# PowerBoard-OLD.net
KiCad netlist of a schematic drawn in Altium Designer
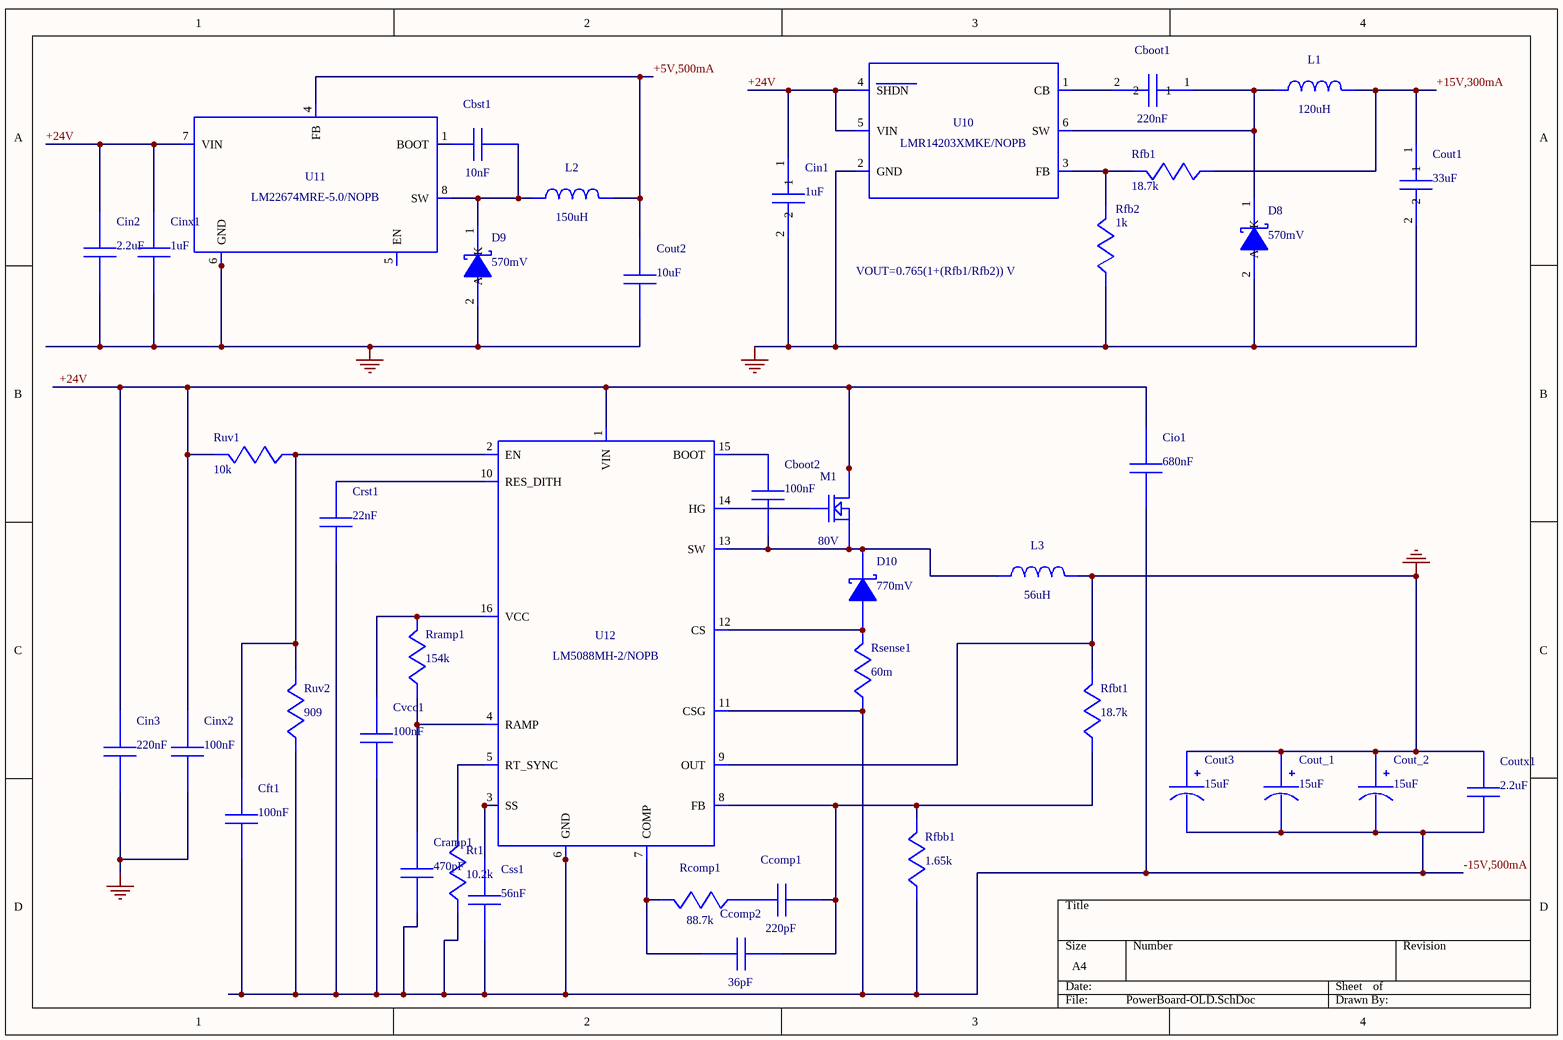
[diagram p0: PowerBoard-OLD.SchDoc]

(export (version "E")
  (design (tool "Eeschema 10.0.6"))
  (components
    (comp (ref "Cboot1")
      (value "220nF")
      (description "GRM155C80G224KE0")
      (fields (field (name "MANUFACTURER PART NUMBER") "GRM155C80G224KE01D"))
      (libsource (lib "TI WEBENCH") (part "Cboot"))
    )
    (comp (ref "Cboot2")
      (value "100nF")
      (description "C0603C104K5RACTU")
      (libsource (lib "") (part "Cboot_1"))
    )
    (comp (ref "Cbst1")
      (value "10nF")
      (description "C0805C103K5RACTU")
      (libsource (lib "TI WEBENCH") (part "Cbst"))
    )
    (comp (ref "Ccomp1")
      (value "220pF")
      (description "CC0805JRNPO9BN22")
      (fields (field (name "MANUFACTURER PART NUMBER") "CC0805JRNPO9BN221"))
      (libsource (lib "TI WEBENCH") (part "Ccomp"))
    )
    (comp (ref "Ccomp2")
      (value "36pF")
      (description "CL21C360JBANNNC")
      (libsource (lib "TI WEBENCH") (part "Ccomp2"))
    )
    (comp (ref "Cft1")
      (value "100nF")
      (description "GRM155R61A104KA0")
      (fields (field (name "MANUFACTURER PART NUMBER") "GRM155R61A104KA01D"))
      (libsource (lib "TI WEBENCH") (part "Cft"))
    )
    (comp (ref "Cin1")
      (value "1uF")
      (description "C1608X5R1H105K08")
      (fields (field (name "MANUFACTURER PART NUMBER") "C1608X5R1H105K080AB"))
      (libsource (lib "") (part "Cin_1"))
    )
    (comp (ref "Cin2")
      (value "2.2uF")
      (description "GRM31CR71H225KA8")
      (fields (field (name "MANUFACTURER PART NUMBER") "GRM31CR71H225KA88L"))
      (libsource (lib "TI WEBENCH") (part "Cin"))
    )
    (comp (ref "Cin3")
      (value "220nF")
      (description "C0805C224K5RACTU")
      (libsource (lib "TI WEBENCH") (part "Cin"))
    )
    (comp (ref "Cinx1")
      (value "1uF")
      (description "C1608X5R1H105K08")
      (fields (field (name "MANUFACTURER PART NUMBER") "C1608X5R1H105K080AB"))
      (libsource (lib "TI WEBENCH") (part "Cinx"))
    )
    (comp (ref "Cinx2")
      (value "100nF")
      (description "C0805C104K5RACTU")
      (libsource (lib "TI WEBENCH") (part "Cinx"))
    )
    (comp (ref "Cio1")
      (value "680nF")
      (description "C2012X7S2A684K12")
      (fields (field (name "MANUFACTURER PART NUMBER") "C2012X7S2A684K125AB"))
      (libsource (lib "TI WEBENCH") (part "Cio"))
    )
    (comp (ref "Cout1")
      (value "33uF")
      (description "C3216X5R1E336M16")
      (fields (field (name "MANUFACTURER PART NUMBER") "C3216X5R1E336M160AC"))
      (libsource (lib "TI WEBENCH") (part "Cout"))
    )
    (comp (ref "Cout2") (value "10uF") (description "C0805C106K8PACTU") (libsource (lib "") (part "Cout_2")))
    (comp (ref "Cout3")
      (value "15uF")
      (description "T495C156K020ATE3")
      (fields (field (name "MANUFACTURER PART NUMBER") "T495C156K020ATE375"))
      (libsource (lib "") (part "Cout_1"))
    )
    (comp (ref "Coutx1")
      (value "2.2uF")
      (description "GRM21BR61E225KA1")
      (fields (field (name "MANUFACTURER PART NUMBER") "GRM21BR61E225KA12L"))
      (libsource (lib "TI WEBENCH") (part "Coutx"))
    )
    (comp (ref "Cout_1")
      (value "15uF")
      (description "T495C156K020ATE3")
      (fields (field (name "MANUFACTURER PART NUMBER") "T495C156K020ATE375"))
      (libsource (lib "TI WEBENCH") (part "Cout_2"))
    )
    (comp (ref "Cout_2")
      (value "15uF")
      (description "T495C156K020ATE3")
      (fields (field (name "MANUFACTURER PART NUMBER") "T495C156K020ATE375"))
      (libsource (lib "TI WEBENCH") (part "Cout_3"))
    )
    (comp (ref "Cramp1")
      (value "470pF")
      (description "CC0805KRX7R9BB47")
      (fields (field (name "MANUFACTURER PART NUMBER") "CC0805KRX7R9BB471"))
      (libsource (lib "TI WEBENCH") (part "Cramp"))
    )
    (comp (ref "Crst1")
      (value "22nF")
      (description "GRM033C80J223KE0")
      (fields (field (name "MANUFACTURER PART NUMBER") "GRM033C80J223KE01D"))
      (libsource (lib "TI WEBENCH") (part "Crst"))
    )
    (comp (ref "Css1")
      (value "56nF")
      (description "GRM155R61A563KA0")
      (fields (field (name "MANUFACTURER PART NUMBER") "GRM155R61A563KA01D"))
      (libsource (lib "TI WEBENCH") (part "Css"))
    )
    (comp (ref "Cvcc1")
      (value "100nF")
      (description "GRM155R61A104KA0")
      (fields (field (name "MANUFACTURER PART NUMBER") "GRM155R61A104KA01D"))
      (libsource (lib "TI WEBENCH") (part "Cvcc"))
    )
    (comp (ref "D8")
      (value "570mV")
      (description "PMEG6010CEH,115")
      (libsource (lib "TI WEBENCH") (part "D1"))
    )
    (comp (ref "D9")
      (value "570mV")
      (description "PMEG6010CEH,115")
      (libsource (lib "TI WEBENCH") (part "D1"))
    )
    (comp (ref "D10") (value "770mV") (description "DFLS1100-7") (libsource (lib "") (part "D1_1")))
    (comp (ref "L1") (value "120uH") (description "NPI75C121KTRF") (libsource (lib "TI WEBENCH") (part "L1")))
    (comp (ref "L2")
      (value "150uH")
      (description "Unknown")
      (fields (field (name "MANUFACTURER PART NUMBER") "VLP8040T-151M"))
      (libsource (lib "TI WEBENCH") (part "L1"))
    )
    (comp (ref "L3") (value "56uH") (description "SDR1307-560KL") (libsource (lib "TI WEBENCH") (part "L1")))
    (comp (ref "M1") (value "80V") (description "BSC340N08NS3 G") (libsource (lib "TI WEBENCH") (part "M1")))
    (comp (ref "Rcomp1")
      (value "88.7k")
      (description "CRCW040288K7FKED")
      (libsource (lib "TI WEBENCH") (part "Rcomp"))
    )
    (comp (ref "Rfb1")
      (value "18.7k")
      (description "CRCW040218K7FKED")
      (libsource (lib "TI WEBENCH") (part "Rfb2"))
    )
    (comp (ref "Rfb2")
      (value "1k")
      (description "CRCW04021K00FKED")
      (libsource (lib "TI WEBENCH") (part "Rfb1"))
    )
    (comp (ref "Rfbb1")
      (value "1.65k")
      (description "CRCW04021K65FKED")
      (libsource (lib "TI WEBENCH") (part "Rfbb"))
    )
    (comp (ref "Rfbt1")
      (value "18.7k")
      (description "CRCW040218K7FKED")
      (libsource (lib "TI WEBENCH") (part "Rfbt"))
    )
    (comp (ref "Rramp1")
      (value "154k")
      (description "CRCW0402154KFKED")
      (libsource (lib "TI WEBENCH") (part "Rramp"))
    )
    (comp (ref "Rsense1")
      (value "60m")
      (description "CSRN2010FK60L0")
      (libsource (lib "TI WEBENCH") (part "Rsense"))
    )
    (comp (ref "Rt1")
      (value "10.2k")
      (description "CRCW040210K2FKED")
      (libsource (lib "TI WEBENCH") (part "Rt"))
    )
    (comp (ref "Ruv1")
      (value "10k")
      (description "CRCW040210K0FKED")
      (libsource (lib "TI WEBENCH") (part "Ruv2"))
    )
    (comp (ref "Ruv2")
      (value "909")
      (description "CRCW0402909RFKED")
      (libsource (lib "TI WEBENCH") (part "Ruv1"))
    )
    (comp (ref "U10")
      (value "LMR14203XMK/NOPB")
      (description "LMR14203XMKE/NOP")
      (fields (field (name "PACKAGEREFERENCE") "LMR14203XMKE/NOPB"))
      (libsource (lib "") (part "U1_1"))
    )
    (comp (ref "U11")
      (value "LM22674MRE-5.0/NOPB")
      (description "LM22674MRE-5.0/N")
      (fields (field (name "PACKAGEREFERENCE") "LM22674MRE-5.0/NOPB"))
      (libsource (lib "TI WEBENCH") (part "U1"))
    )
    (comp (ref "U12")
      (value "LM5088MH-2/NOPB")
      (fields (field (name "PACKAGEREFERENCE") "LM5088MH-2/NOPB"))
      (libsource (lib "") (part "U1_2"))
    )
  )
  (nets
    (net (code "1") (name "/+5V,500mA") (class "Default")
      (node (ref "Cout2") (pin "1") (pinfunction "1_1") (pintype "passive"))
      (node (ref "L2") (pin "2") (pinfunction "2_2") (pintype "passive"))
      (node (ref "U11") (pin "4") (pinfunction "FB_4") (pintype "passive"))
    )
    (net (code "2") (name "/+15V,300mA") (class "Default")
      (node (ref "Cout1") (pin "1") (pinfunction "1_1") (pintype "passive"))
      (node (ref "L1") (pin "2") (pinfunction "2_2") (pintype "passive"))
      (node (ref "Rfb1") (pin "2") (pinfunction "2_2") (pintype "passive"))
    )
    (net (code "3") (name "/+24V") (class "Default")
      (node (ref "Cin1") (pin "1") (pinfunction "1_1") (pintype "passive"))
      (node (ref "Cin2") (pin "1") (pinfunction "1_1") (pintype "passive"))
      (node (ref "Cin3") (pin "1") (pinfunction "1_1") (pintype "passive"))
      (node (ref "Cinx1") (pin "1") (pinfunction "1_1") (pintype "passive"))
      (node (ref "Cinx2") (pin "1") (pinfunction "1_1") (pintype "passive"))
      (node (ref "Cio1") (pin "1") (pinfunction "1_1") (pintype "passive"))
      (node (ref "M1") (pin "5") (pinfunction "Drain_5") (pintype "passive"))
      (node (ref "M1") (pin "6") (pinfunction "Drain_6") (pintype "passive"))
      (node (ref "M1") (pin "7") (pinfunction "Drain_7") (pintype "passive"))
      (node (ref "M1") (pin "8") (pinfunction "Drain_8") (pintype "passive"))
      (node (ref "M1") (pin "9") (pinfunction "Drain_9") (pintype "passive"))
      (node (ref "Ruv1") (pin "1") (pinfunction "1_1") (pintype "passive"))
      (node (ref "U10") (pin "4") (pinfunction "SHDN_4") (pintype "passive"))
      (node (ref "U10") (pin "5") (pinfunction "VIN_5") (pintype "passive"))
      (node (ref "U11") (pin "7") (pinfunction "VIN_7") (pintype "passive"))
      (node (ref "U12") (pin "1") (pinfunction "VIN_1") (pintype "passive"))
    )
    (net (code "4") (name "/-15V,500mA") (class "Default")
      (node (ref "Cft1") (pin "2") (pinfunction "2_2") (pintype "passive"))
      (node (ref "Cio1") (pin "2") (pinfunction "2_2") (pintype "passive"))
      (node (ref "Cout3") (pin "2") (pinfunction "-_2") (pintype "passive"))
      (node (ref "Cout_1") (pin "2") (pinfunction "-_2") (pintype "passive"))
      (node (ref "Cout_2") (pin "2") (pinfunction "-_2") (pintype "passive"))
      (node (ref "Coutx1") (pin "2") (pinfunction "2_2") (pintype "passive"))
      (node (ref "Cramp1") (pin "2") (pinfunction "2_2") (pintype "passive"))
      (node (ref "Crst1") (pin "2") (pinfunction "2_2") (pintype "passive"))
      (node (ref "Css1") (pin "2") (pinfunction "2_2") (pintype "passive"))
      (node (ref "Cvcc1") (pin "2") (pinfunction "2_2") (pintype "passive"))
      (node (ref "Rfbb1") (pin "2") (pinfunction "2_2") (pintype "passive"))
      (node (ref "Rsense1") (pin "2") (pinfunction "2_2") (pintype "passive"))
      (node (ref "Rt1") (pin "2") (pinfunction "2_2") (pintype "passive"))
      (node (ref "Ruv2") (pin "2") (pinfunction "2_2") (pintype "passive"))
      (node (ref "U12") (pin "11") (pinfunction "CSG_11") (pintype "passive"))
      (node (ref "U12") (pin "17") (pinfunction "EP_17") (pintype "passive"))
      (node (ref "U12") (pin "6") (pinfunction "GND_6") (pintype "passive"))
    )
    (net (code "5") (name "0") (class "Default")
      (node (ref "Cin1") (pin "2") (pinfunction "2_2") (pintype "passive"))
      (node (ref "Cin2") (pin "2") (pinfunction "2_2") (pintype "passive"))
      (node (ref "Cin3") (pin "2") (pinfunction "2_2") (pintype "passive"))
      (node (ref "Cinx1") (pin "2") (pinfunction "2_2") (pintype "passive"))
      (node (ref "Cinx2") (pin "2") (pinfunction "2_2") (pintype "passive"))
      (node (ref "Cout1") (pin "2") (pinfunction "2_2") (pintype "passive"))
      (node (ref "Cout2") (pin "2") (pinfunction "2_2") (pintype "passive"))
      (node (ref "Cout3") (pin "1") (pinfunction "+_1") (pintype "passive"))
      (node (ref "Cout_1") (pin "1") (pinfunction "+_1") (pintype "passive"))
      (node (ref "Cout_2") (pin "1") (pinfunction "+_1") (pintype "passive"))
      (node (ref "Coutx1") (pin "1") (pinfunction "1_1") (pintype "passive"))
      (node (ref "D8") (pin "2") (pinfunction "A_2") (pintype "passive"))
      (node (ref "D9") (pin "2") (pinfunction "A_2") (pintype "passive"))
      (node (ref "L3") (pin "2") (pinfunction "2_2") (pintype "passive"))
      (node (ref "Rfb2") (pin "2") (pinfunction "2_2") (pintype "passive"))
      (node (ref "Rfbt1") (pin "1") (pinfunction "1_1") (pintype "passive"))
      (node (ref "U10") (pin "2") (pinfunction "GND_2") (pintype "passive"))
      (node (ref "U11") (pin "2") (pinfunction "NC_2") (pintype "passive"))
      (node (ref "U11") (pin "3") (pinfunction "NC_3") (pintype "passive"))
      (node (ref "U11") (pin "6") (pinfunction "GND_6") (pintype "passive"))
      (node (ref "U11") (pin "9") (pinfunction "DAP_9") (pintype "passive"))
      (node (ref "U12") (pin "9") (pinfunction "OUT_9") (pintype "passive"))
    )
    (net (code "6") (name "Net-(Ccomp1-Pad1)") (class "Default")
      (node (ref "Ccomp1") (pin "1") (pinfunction "1_1") (pintype "passive"))
      (node (ref "Rcomp1") (pin "2") (pinfunction "2_2") (pintype "passive"))
    )
    (net (code "7") (name "Net-(D8-K)") (class "Default")
      (node (ref "Cboot1") (pin "1") (pinfunction "1_1") (pintype "passive"))
      (node (ref "D8") (pin "1") (pinfunction "K_1") (pintype "passive"))
      (node (ref "L1") (pin "1") (pinfunction "1_1") (pintype "passive"))
      (node (ref "U10") (pin "6") (pinfunction "SW_6") (pintype "passive"))
    )
    (net (code "8") (name "Net-(D9-K)") (class "Default")
      (node (ref "Cbst1") (pin "1") (pinfunction "1_1") (pintype "passive"))
      (node (ref "D9") (pin "1") (pinfunction "K_1") (pintype "passive"))
      (node (ref "L2") (pin "1") (pinfunction "1_1") (pintype "passive"))
      (node (ref "U11") (pin "8") (pinfunction "SW_8") (pintype "passive"))
    )
    (net (code "9") (name "Net-(D10-A)") (class "Default")
      (node (ref "D10") (pin "2") (pinfunction "A_2") (pintype "passive"))
      (node (ref "Rsense1") (pin "1") (pinfunction "1_1") (pintype "passive"))
      (node (ref "U12") (pin "12") (pinfunction "CS_12") (pintype "passive"))
    )
    (net (code "10") (name "Net-(D10-K)") (class "Default")
      (node (ref "Cboot2") (pin "1") (pinfunction "1_1") (pintype "passive"))
      (node (ref "D10") (pin "1") (pinfunction "K_1") (pintype "passive"))
      (node (ref "L3") (pin "1") (pinfunction "1_1") (pintype "passive"))
      (node (ref "M1") (pin "1") (pinfunction "Source_1") (pintype "passive"))
      (node (ref "M1") (pin "2") (pinfunction "Source_2") (pintype "passive"))
      (node (ref "M1") (pin "3") (pinfunction "Source_3") (pintype "passive"))
      (node (ref "U12") (pin "13") (pinfunction "SW_13") (pintype "passive"))
    )
    (net (code "11") (name "Net-(M1-Gate)") (class "Default")
      (node (ref "M1") (pin "4") (pinfunction "Gate_4") (pintype "passive"))
      (node (ref "U12") (pin "14") (pinfunction "HG_14") (pintype "passive"))
    )
    (net (code "12") (name "Net-(U10-CB)") (class "Default")
      (node (ref "Cboot1") (pin "2") (pinfunction "2_2") (pintype "passive"))
      (node (ref "U10") (pin "1") (pinfunction "CB_1") (pintype "passive"))
    )
    (net (code "13") (name "Net-(U10-FB)") (class "Default")
      (node (ref "Rfb1") (pin "1") (pinfunction "1_1") (pintype "passive"))
      (node (ref "Rfb2") (pin "1") (pinfunction "1_1") (pintype "passive"))
      (node (ref "U10") (pin "3") (pinfunction "FB_3") (pintype "passive"))
    )
    (net (code "14") (name "Net-(U11-BOOT)") (class "Default")
      (node (ref "Cbst1") (pin "2") (pinfunction "2_2") (pintype "passive"))
      (node (ref "U11") (pin "1") (pinfunction "BOOT_1") (pintype "passive"))
    )
    (net (code "15") (name "Net-(U12-BOOT)") (class "Default")
      (node (ref "Cboot2") (pin "2") (pinfunction "2_2") (pintype "passive"))
      (node (ref "U12") (pin "15") (pinfunction "BOOT_15") (pintype "passive"))
    )
    (net (code "16") (name "Net-(U12-COMP)") (class "Default")
      (node (ref "Ccomp2") (pin "1") (pinfunction "1_1") (pintype "passive"))
      (node (ref "Rcomp1") (pin "1") (pinfunction "1_1") (pintype "passive"))
      (node (ref "U12") (pin "7") (pinfunction "COMP_7") (pintype "passive"))
    )
    (net (code "17") (name "Net-(U12-EN)") (class "Default")
      (node (ref "Cft1") (pin "1") (pinfunction "1_1") (pintype "passive"))
      (node (ref "Ruv1") (pin "2") (pinfunction "2_2") (pintype "passive"))
      (node (ref "Ruv2") (pin "1") (pinfunction "1_1") (pintype "passive"))
      (node (ref "U12") (pin "2") (pinfunction "EN_2") (pintype "passive"))
    )
    (net (code "18") (name "Net-(U12-FB)") (class "Default")
      (node (ref "Ccomp1") (pin "2") (pinfunction "2_2") (pintype "passive"))
      (node (ref "Ccomp2") (pin "2") (pinfunction "2_2") (pintype "passive"))
      (node (ref "Rfbb1") (pin "1") (pinfunction "1_1") (pintype "passive"))
      (node (ref "Rfbt1") (pin "2") (pinfunction "2_2") (pintype "passive"))
      (node (ref "U12") (pin "8") (pinfunction "FB_8") (pintype "passive"))
    )
    (net (code "19") (name "Net-(U12-RAMP)") (class "Default")
      (node (ref "Cramp1") (pin "1") (pinfunction "1_1") (pintype "passive"))
      (node (ref "Rramp1") (pin "2") (pinfunction "2_2") (pintype "passive"))
      (node (ref "U12") (pin "4") (pinfunction "RAMP_4") (pintype "passive"))
    )
    (net (code "20") (name "Net-(U12-RES_DITH)") (class "Default")
      (node (ref "Crst1") (pin "1") (pinfunction "1_1") (pintype "passive"))
      (node (ref "U12") (pin "10") (pinfunction "RES_DITH_10") (pintype "passive"))
    )
    (net (code "21") (name "Net-(U12-RT_SYNC)") (class "Default")
      (node (ref "Rt1") (pin "1") (pinfunction "1_1") (pintype "passive"))
      (node (ref "U12") (pin "5") (pinfunction "RT_SYNC_5") (pintype "passive"))
    )
    (net (code "22") (name "Net-(U12-SS)") (class "Default")
      (node (ref "Css1") (pin "1") (pinfunction "1_1") (pintype "passive"))
      (node (ref "U12") (pin "3") (pinfunction "SS_3") (pintype "passive"))
    )
    (net (code "23") (name "Net-(U12-VCC)") (class "Default")
      (node (ref "Cvcc1") (pin "1") (pinfunction "1_1") (pintype "passive"))
      (node (ref "Rramp1") (pin "1") (pinfunction "1_1") (pintype "passive"))
      (node (ref "U12") (pin "16") (pinfunction "VCC_16") (pintype "passive"))
    )
    (net (code "24") (name "unconnected-(U11-EN-Pad5)") (class "Default")
      (node (ref "U11") (pin "5") (pinfunction "EN_5") (pintype "passive"))
    )
  )
)
